# LEDS_And_Buttons.net
KiCad netlist of a schematic drawn in Altium Designer
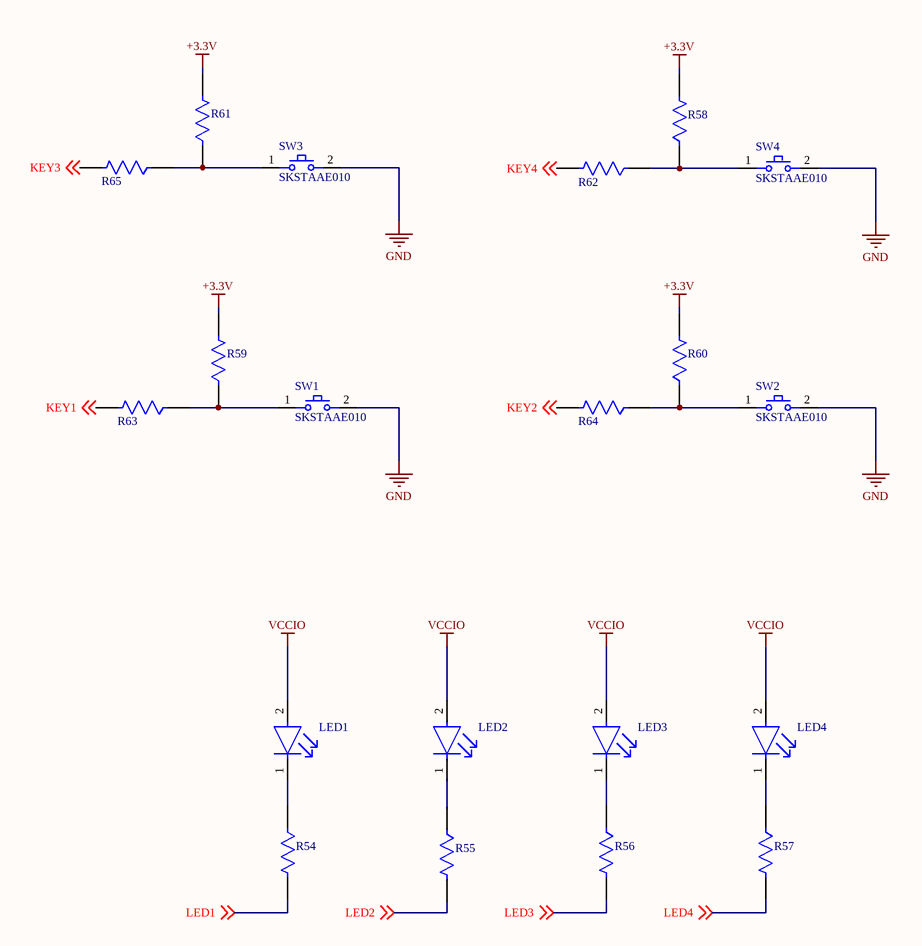
[diagram p0: LEDS_And_Buttons.SchDoc]

(export (version "E")
  (design (tool "Eeschema 10.0.6"))
  (components
    (comp (ref "LED1")
      (value "LTST-C230EKT")
      (footprint "FP-LTST-C230EKT-MFG")
      (description "LED RED CLEAR CHIP SMD")
      (libsource (lib "Altium Content Vault") (part "8706943c75ba83719d021d2fdc84c58"))
    )
    (comp (ref "LED2")
      (value "LTST-C230EKT")
      (footprint "FP-LTST-C230EKT-MFG")
      (description "LED RED CLEAR CHIP SMD")
      (libsource (lib "Altium Content Vault") (part "8706943c75ba83719d021d2fdc84c58"))
    )
    (comp (ref "LED3")
      (value "LTST-C230EKT")
      (footprint "FP-LTST-C230EKT-MFG")
      (description "LED RED CLEAR CHIP SMD")
      (libsource (lib "Altium Content Vault") (part "8706943c75ba83719d021d2fdc84c58"))
    )
    (comp (ref "LED4")
      (value "LTST-C230EKT")
      (footprint "FP-LTST-C230EKT-MFG")
      (description "LED RED CLEAR CHIP SMD")
      (libsource (lib "Altium Content Vault") (part "8706943c75ba83719d021d2fdc84c58"))
    )
    (comp (ref "R54")
      (value "MCU0805MD4991BP100")
      (footprint "FP-MCU0805-MFG")
      (description "RES 1.05K OHM 0.5% 1/5W 0805")
      (fields (field (name "TOLERANCE") "0.1%"))
      (libsource (lib "Altium Content Vault") (part "1029c3af85768c4190bb7ad29bc67b5"))
    )
    (comp (ref "R55")
      (value "MCU0805MD4991BP100")
      (footprint "FP-MCU0805-MFG")
      (description "RES 1.05K OHM 0.5% 1/5W 0805")
      (fields (field (name "TOLERANCE") "0.1%"))
      (libsource (lib "Altium Content Vault") (part "1029c3af85768c4190bb7ad29bc67b5"))
    )
    (comp (ref "R56")
      (value "MCU0805MD4991BP100")
      (footprint "FP-MCU0805-MFG")
      (description "RES 1.05K OHM 0.5% 1/5W 0805")
      (fields (field (name "TOLERANCE") "0.1%"))
      (libsource (lib "Altium Content Vault") (part "1029c3af85768c4190bb7ad29bc67b5"))
    )
    (comp (ref "R57")
      (value "MCU0805MD4991BP100")
      (footprint "FP-MCU0805-MFG")
      (description "RES 1.05K OHM 0.5% 1/5W 0805")
      (fields (field (name "TOLERANCE") "0.1%"))
      (libsource (lib "Altium Content Vault") (part "1029c3af85768c4190bb7ad29bc67b5"))
    )
    (comp (ref "R58")
      (value "MCU0805MD4991BP100")
      (footprint "FP-MCU0805-MFG")
      (description "RES 1.05K OHM 0.5% 1/5W 0805")
      (fields (field (name "TOLERANCE") "0.1%"))
      (libsource (lib "Altium Content Vault") (part "1029c3af85768c4190bb7ad29bc67b5"))
    )
    (comp (ref "R59")
      (value "MCU0805MD4991BP100")
      (footprint "FP-MCU0805-MFG")
      (description "RES 1.05K OHM 0.5% 1/5W 0805")
      (fields (field (name "TOLERANCE") "0.1%"))
      (libsource (lib "Altium Content Vault") (part "1029c3af85768c4190bb7ad29bc67b5"))
    )
    (comp (ref "R60")
      (value "MCU0805MD4991BP100")
      (footprint "FP-MCU0805-MFG")
      (description "RES 1.05K OHM 0.5% 1/5W 0805")
      (fields (field (name "TOLERANCE") "0.1%"))
      (libsource (lib "Altium Content Vault") (part "1029c3af85768c4190bb7ad29bc67b5"))
    )
    (comp (ref "R61")
      (value "MCU0805MD4991BP100")
      (footprint "FP-MCU0805-MFG")
      (description "RES 1.05K OHM 0.5% 1/5W 0805")
      (fields (field (name "TOLERANCE") "0.1%"))
      (libsource (lib "Altium Content Vault") (part "1029c3af85768c4190bb7ad29bc67b5"))
    )
    (comp (ref "R62")
      (value "MCU0805MD4991BP100")
      (footprint "FP-MCU0805-MFG")
      (description "RES 1.05K OHM 0.5% 1/5W 0805")
      (fields (field (name "TOLERANCE") "0.1%"))
      (libsource (lib "Altium Content Vault") (part "1029c3af85768c4190bb7ad29bc67b5"))
    )
    (comp (ref "R63")
      (value "MCU0805MD4991BP100")
      (footprint "FP-MCU0805-MFG")
      (description "RES 1.05K OHM 0.5% 1/5W 0805")
      (fields (field (name "TOLERANCE") "0.1%"))
      (libsource (lib "Altium Content Vault") (part "1029c3af85768c4190bb7ad29bc67b5"))
    )
    (comp (ref "R64")
      (value "MCU0805MD4991BP100")
      (footprint "FP-MCU0805-MFG")
      (description "RES 1.05K OHM 0.5% 1/5W 0805")
      (fields (field (name "TOLERANCE") "0.1%"))
      (libsource (lib "Altium Content Vault") (part "1029c3af85768c4190bb7ad29bc67b5"))
    )
    (comp (ref "R65")
      (value "MCU0805MD4991BP100")
      (footprint "FP-MCU0805-MFG")
      (description "RES 1.05K OHM 0.5% 1/5W 0805")
      (fields (field (name "TOLERANCE") "0.1%"))
      (libsource (lib "Altium Content Vault") (part "1029c3af85768c4190bb7ad29bc67b5"))
    )
    (comp (ref "SW1")
      (value "SKSTAAE010")
      (footprint "FP-SKSTAAE010-MFG")
      (description "Tactile Switches Quiet 0.9mm Middle Stroke, 4N,500KCycle")
      (libsource (lib "Altium Content Vault") (part "69e8347f6a24c021ef43a914a4df441"))
    )
    (comp (ref "SW2")
      (value "SKSTAAE010")
      (footprint "FP-SKSTAAE010-MFG")
      (description "Tactile Switches Quiet 0.9mm Middle Stroke, 4N,500KCycle")
      (libsource (lib "Altium Content Vault") (part "69e8347f6a24c021ef43a914a4df441"))
    )
    (comp (ref "SW3")
      (value "SKSTAAE010")
      (footprint "FP-SKSTAAE010-MFG")
      (description "Tactile Switches Quiet 0.9mm Middle Stroke, 4N,500KCycle")
      (libsource (lib "Altium Content Vault") (part "69e8347f6a24c021ef43a914a4df441"))
    )
    (comp (ref "SW4")
      (value "SKSTAAE010")
      (footprint "FP-SKSTAAE010-MFG")
      (description "Tactile Switches Quiet 0.9mm Middle Stroke, 4N,500KCycle")
      (libsource (lib "Altium Content Vault") (part "69e8347f6a24c021ef43a914a4df441"))
    )
  )
  (nets
    (net (code "1") (name "+3.3V") (class "Default")
      (node (ref "R58") (pin "2") (pinfunction "2_2") (pintype "passive"))
      (node (ref "R59") (pin "2") (pinfunction "2_2") (pintype "passive"))
      (node (ref "R60") (pin "2") (pinfunction "2_2") (pintype "passive"))
      (node (ref "R61") (pin "2") (pinfunction "2_2") (pintype "passive"))
    )
    (net (code "2") (name "GND") (class "Default")
      (node (ref "SW1") (pin "2") (pinfunction "2_2") (pintype "passive"))
      (node (ref "SW2") (pin "2") (pinfunction "2_2") (pintype "passive"))
      (node (ref "SW3") (pin "2") (pinfunction "2_2") (pintype "passive"))
      (node (ref "SW4") (pin "2") (pinfunction "2_2") (pintype "passive"))
    )
    (net (code "3") (name "KEY1") (class "Default")
      (node (ref "R63") (pin "2") (pinfunction "2_2") (pintype "passive"))
    )
    (net (code "4") (name "KEY2") (class "Default")
      (node (ref "R64") (pin "2") (pinfunction "2_2") (pintype "passive"))
    )
    (net (code "5") (name "KEY3") (class "Default")
      (node (ref "R65") (pin "2") (pinfunction "2_2") (pintype "passive"))
    )
    (net (code "6") (name "KEY4") (class "Default")
      (node (ref "R62") (pin "2") (pinfunction "2_2") (pintype "passive"))
    )
    (net (code "7") (name "LED1") (class "Default")
      (node (ref "R54") (pin "2") (pinfunction "2_2") (pintype "passive"))
    )
    (net (code "8") (name "LED2") (class "Default")
      (node (ref "R55") (pin "2") (pinfunction "2_2") (pintype "passive"))
    )
    (net (code "9") (name "LED3") (class "Default")
      (node (ref "R56") (pin "2") (pinfunction "2_2") (pintype "passive"))
    )
    (net (code "10") (name "LED4") (class "Default")
      (node (ref "R57") (pin "2") (pinfunction "2_2") (pintype "passive"))
    )
    (net (code "11") (name "Net-(LED1-C)") (class "Default")
      (node (ref "LED1") (pin "1") (pinfunction "C_1") (pintype "passive"))
      (node (ref "R54") (pin "1") (pinfunction "1_1") (pintype "passive"))
    )
    (net (code "12") (name "Net-(LED2-C)") (class "Default")
      (node (ref "LED2") (pin "1") (pinfunction "C_1") (pintype "passive"))
      (node (ref "R55") (pin "1") (pinfunction "1_1") (pintype "passive"))
    )
    (net (code "13") (name "Net-(LED3-C)") (class "Default")
      (node (ref "LED3") (pin "1") (pinfunction "C_1") (pintype "passive"))
      (node (ref "R56") (pin "1") (pinfunction "1_1") (pintype "passive"))
    )
    (net (code "14") (name "Net-(LED4-C)") (class "Default")
      (node (ref "LED4") (pin "1") (pinfunction "C_1") (pintype "passive"))
      (node (ref "R57") (pin "1") (pinfunction "1_1") (pintype "passive"))
    )
    (net (code "15") (name "Net-(R58-Pad1)") (class "Default")
      (node (ref "R58") (pin "1") (pinfunction "1_1") (pintype "passive"))
      (node (ref "R62") (pin "1") (pinfunction "1_1") (pintype "passive"))
      (node (ref "SW4") (pin "1") (pinfunction "1_1") (pintype "passive"))
    )
    (net (code "16") (name "Net-(R59-Pad1)") (class "Default")
      (node (ref "R59") (pin "1") (pinfunction "1_1") (pintype "passive"))
      (node (ref "R63") (pin "1") (pinfunction "1_1") (pintype "passive"))
      (node (ref "SW1") (pin "1") (pinfunction "1_1") (pintype "passive"))
    )
    (net (code "17") (name "Net-(R60-Pad1)") (class "Default")
      (node (ref "R60") (pin "1") (pinfunction "1_1") (pintype "passive"))
      (node (ref "R64") (pin "1") (pinfunction "1_1") (pintype "passive"))
      (node (ref "SW2") (pin "1") (pinfunction "1_1") (pintype "passive"))
    )
    (net (code "18") (name "Net-(R61-Pad1)") (class "Default")
      (node (ref "R61") (pin "1") (pinfunction "1_1") (pintype "passive"))
      (node (ref "R65") (pin "1") (pinfunction "1_1") (pintype "passive"))
      (node (ref "SW3") (pin "1") (pinfunction "1_1") (pintype "passive"))
    )
    (net (code "19") (name "VCCIO") (class "Default")
      (node (ref "LED1") (pin "2") (pinfunction "A_2") (pintype "passive"))
      (node (ref "LED2") (pin "2") (pinfunction "A_2") (pintype "passive"))
      (node (ref "LED3") (pin "2") (pinfunction "A_2") (pintype "passive"))
      (node (ref "LED4") (pin "2") (pinfunction "A_2") (pintype "passive"))
    )
  )
)
